# ledDisplay.net
KiCad netlist of a schematic drawn in EAGLE
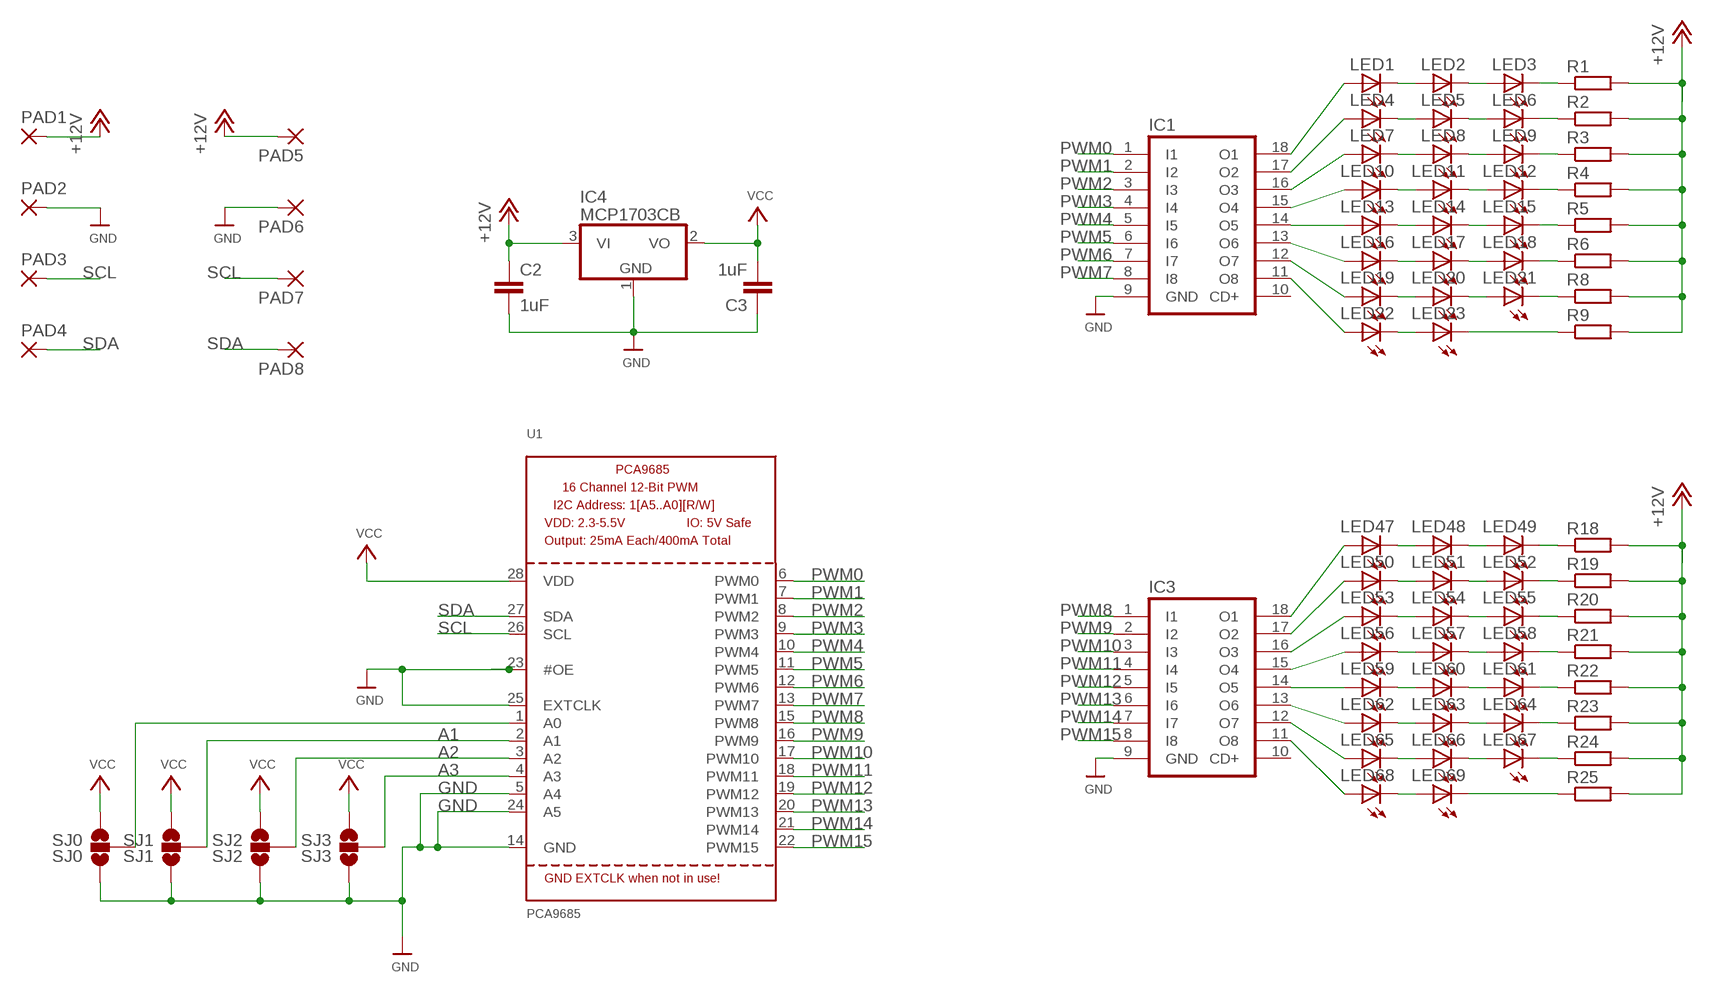
[diagram p0: schematic, sheet 1]

(export (version "E")
  (design (tool "Eeschema 10.0.6"))
  (components
    (comp (ref "C2")
      (value "1uF")
      (footprint "eagle-import:C1206")
      (libsource (lib "eagle-import") (part "C-EUC1206"))
    )
    (comp (ref "C3")
      (value "1uF")
      (footprint "eagle-import:C1206")
      (libsource (lib "eagle-import") (part "C-EUC1206"))
    )
    (comp (ref "IC1")
      (value "ULN2803A")
      (footprint "eagle-import:SO18W")
      (libsource (lib "eagle-import") (part "ULN2803A"))
    )
    (comp (ref "IC3")
      (value "ULN2803AIC")
      (footprint "eagle-import:DIL18")
      (libsource (lib "eagle-import") (part "ULN2803AIC"))
    )
    (comp (ref "IC4")
      (value "MCP1703CB")
      (footprint "eagle-import:SOT23")
      (libsource (lib "eagle-import") (part "MCP1703CB"))
    )
    (comp (ref "LED1")
      (value "LED5MM")
      (footprint "eagle-import:LED5MM")
      (libsource (lib "eagle-import") (part "LED5MM"))
    )
    (comp (ref "LED2")
      (value "LED5MM")
      (footprint "eagle-import:LED5MM")
      (libsource (lib "eagle-import") (part "LED5MM"))
    )
    (comp (ref "LED3")
      (value "LED5MM")
      (footprint "eagle-import:LED5MM")
      (libsource (lib "eagle-import") (part "LED5MM"))
    )
    (comp (ref "LED4")
      (value "LED5MM")
      (footprint "eagle-import:LED5MM")
      (libsource (lib "eagle-import") (part "LED5MM"))
    )
    (comp (ref "LED5")
      (value "LED5MM")
      (footprint "eagle-import:LED5MM")
      (libsource (lib "eagle-import") (part "LED5MM"))
    )
    (comp (ref "LED6")
      (value "LED5MM")
      (footprint "eagle-import:LED5MM")
      (libsource (lib "eagle-import") (part "LED5MM"))
    )
    (comp (ref "LED7")
      (value "LED5MM")
      (footprint "eagle-import:LED5MM")
      (libsource (lib "eagle-import") (part "LED5MM"))
    )
    (comp (ref "LED8")
      (value "LED5MM")
      (footprint "eagle-import:LED5MM")
      (libsource (lib "eagle-import") (part "LED5MM"))
    )
    (comp (ref "LED9")
      (value "LED5MM")
      (footprint "eagle-import:LED5MM")
      (libsource (lib "eagle-import") (part "LED5MM"))
    )
    (comp (ref "LED10")
      (value "LED5MM")
      (footprint "eagle-import:LED5MM")
      (libsource (lib "eagle-import") (part "LED5MM"))
    )
    (comp (ref "LED11")
      (value "LED5MM")
      (footprint "eagle-import:LED5MM")
      (libsource (lib "eagle-import") (part "LED5MM"))
    )
    (comp (ref "LED12")
      (value "LED5MM")
      (footprint "eagle-import:LED5MM")
      (libsource (lib "eagle-import") (part "LED5MM"))
    )
    (comp (ref "LED13")
      (value "LED5MM")
      (footprint "eagle-import:LED5MM")
      (libsource (lib "eagle-import") (part "LED5MM"))
    )
    (comp (ref "LED14")
      (value "LED5MM")
      (footprint "eagle-import:LED5MM")
      (libsource (lib "eagle-import") (part "LED5MM"))
    )
    (comp (ref "LED15")
      (value "LED5MM")
      (footprint "eagle-import:LED5MM")
      (libsource (lib "eagle-import") (part "LED5MM"))
    )
    (comp (ref "LED16")
      (value "LED5MM")
      (footprint "eagle-import:LED5MM")
      (libsource (lib "eagle-import") (part "LED5MM"))
    )
    (comp (ref "LED17")
      (value "LED5MM")
      (footprint "eagle-import:LED5MM")
      (libsource (lib "eagle-import") (part "LED5MM"))
    )
    (comp (ref "LED18")
      (value "LED5MM")
      (footprint "eagle-import:LED5MM")
      (libsource (lib "eagle-import") (part "LED5MM"))
    )
    (comp (ref "LED19")
      (value "LED5MM")
      (footprint "eagle-import:LED5MM")
      (libsource (lib "eagle-import") (part "LED5MM"))
    )
    (comp (ref "LED20")
      (value "LED5MM")
      (footprint "eagle-import:LED5MM")
      (libsource (lib "eagle-import") (part "LED5MM"))
    )
    (comp (ref "LED21")
      (value "LED5MM")
      (footprint "eagle-import:LED5MM")
      (libsource (lib "eagle-import") (part "LED5MM"))
    )
    (comp (ref "LED22")
      (value "LED5MM")
      (footprint "eagle-import:LED5MM")
      (libsource (lib "eagle-import") (part "LED5MM"))
    )
    (comp (ref "LED23")
      (value "LED5MM")
      (footprint "eagle-import:LED5MM")
      (libsource (lib "eagle-import") (part "LED5MM"))
    )
    (comp (ref "LED47")
      (value "LED5MM")
      (footprint "eagle-import:LED5MM")
      (libsource (lib "eagle-import") (part "LED5MM"))
    )
    (comp (ref "LED48")
      (value "LED5MM")
      (footprint "eagle-import:LED5MM")
      (libsource (lib "eagle-import") (part "LED5MM"))
    )
    (comp (ref "LED49")
      (value "LED5MM")
      (footprint "eagle-import:LED5MM")
      (libsource (lib "eagle-import") (part "LED5MM"))
    )
    (comp (ref "LED50")
      (value "LED5MM")
      (footprint "eagle-import:LED5MM")
      (libsource (lib "eagle-import") (part "LED5MM"))
    )
    (comp (ref "LED51")
      (value "LED5MM")
      (footprint "eagle-import:LED5MM")
      (libsource (lib "eagle-import") (part "LED5MM"))
    )
    (comp (ref "LED52")
      (value "LED5MM")
      (footprint "eagle-import:LED5MM")
      (libsource (lib "eagle-import") (part "LED5MM"))
    )
    (comp (ref "LED53")
      (value "LED5MM")
      (footprint "eagle-import:LED5MM")
      (libsource (lib "eagle-import") (part "LED5MM"))
    )
    (comp (ref "LED54")
      (value "LED5MM")
      (footprint "eagle-import:LED5MM")
      (libsource (lib "eagle-import") (part "LED5MM"))
    )
    (comp (ref "LED55")
      (value "LED5MM")
      (footprint "eagle-import:LED5MM")
      (libsource (lib "eagle-import") (part "LED5MM"))
    )
    (comp (ref "LED56")
      (value "LED5MM")
      (footprint "eagle-import:LED5MM")
      (libsource (lib "eagle-import") (part "LED5MM"))
    )
    (comp (ref "LED57")
      (value "LED5MM")
      (footprint "eagle-import:LED5MM")
      (libsource (lib "eagle-import") (part "LED5MM"))
    )
    (comp (ref "LED58")
      (value "LED5MM")
      (footprint "eagle-import:LED5MM")
      (libsource (lib "eagle-import") (part "LED5MM"))
    )
    (comp (ref "LED59")
      (value "LED5MM")
      (footprint "eagle-import:LED5MM")
      (libsource (lib "eagle-import") (part "LED5MM"))
    )
    (comp (ref "LED60")
      (value "LED5MM")
      (footprint "eagle-import:LED5MM")
      (libsource (lib "eagle-import") (part "LED5MM"))
    )
    (comp (ref "LED61")
      (value "LED5MM")
      (footprint "eagle-import:LED5MM")
      (libsource (lib "eagle-import") (part "LED5MM"))
    )
    (comp (ref "LED62")
      (value "LED5MM")
      (footprint "eagle-import:LED5MM")
      (libsource (lib "eagle-import") (part "LED5MM"))
    )
    (comp (ref "LED63")
      (value "LED5MM")
      (footprint "eagle-import:LED5MM")
      (libsource (lib "eagle-import") (part "LED5MM"))
    )
    (comp (ref "LED64")
      (value "LED5MM")
      (footprint "eagle-import:LED5MM")
      (libsource (lib "eagle-import") (part "LED5MM"))
    )
    (comp (ref "LED65")
      (value "LED5MM")
      (footprint "eagle-import:LED5MM")
      (libsource (lib "eagle-import") (part "LED5MM"))
    )
    (comp (ref "LED66")
      (value "LED5MM")
      (footprint "eagle-import:LED5MM")
      (libsource (lib "eagle-import") (part "LED5MM"))
    )
    (comp (ref "LED67")
      (value "LED5MM")
      (footprint "eagle-import:LED5MM")
      (libsource (lib "eagle-import") (part "LED5MM"))
    )
    (comp (ref "LED68")
      (value "LED5MM")
      (footprint "eagle-import:LED5MM")
      (libsource (lib "eagle-import") (part "LED5MM"))
    )
    (comp (ref "LED69")
      (value "LED5MM")
      (footprint "eagle-import:LED5MM")
      (libsource (lib "eagle-import") (part "LED5MM"))
    )
    (comp (ref "PAD1")
      (value "SMD5")
      (footprint "eagle-import:SMD2,54-5,08")
      (libsource (lib "eagle-import") (part "SMD5"))
    )
    (comp (ref "PAD2")
      (value "SMD5")
      (footprint "eagle-import:SMD2,54-5,08")
      (libsource (lib "eagle-import") (part "SMD5"))
    )
    (comp (ref "PAD3")
      (value "SMD5")
      (footprint "eagle-import:SMD2,54-5,08")
      (libsource (lib "eagle-import") (part "SMD5"))
    )
    (comp (ref "PAD4")
      (value "SMD5")
      (footprint "eagle-import:SMD2,54-5,08")
      (libsource (lib "eagle-import") (part "SMD5"))
    )
    (comp (ref "PAD5")
      (value "SMD5")
      (footprint "eagle-import:SMD2,54-5,08")
      (libsource (lib "eagle-import") (part "SMD5"))
    )
    (comp (ref "PAD6")
      (value "SMD5")
      (footprint "eagle-import:SMD2,54-5,08")
      (libsource (lib "eagle-import") (part "SMD5"))
    )
    (comp (ref "PAD7")
      (value "SMD5")
      (footprint "eagle-import:SMD2,54-5,08")
      (libsource (lib "eagle-import") (part "SMD5"))
    )
    (comp (ref "PAD8")
      (value "SMD5")
      (footprint "eagle-import:SMD2,54-5,08")
      (libsource (lib "eagle-import") (part "SMD5"))
    )
    (comp (ref "R1")
      (value "R-EU_0204/7")
      (footprint "eagle-import:0204_7")
      (libsource (lib "eagle-import") (part "R-EU_0204/7"))
    )
    (comp (ref "R2")
      (value "R-EU_0204/7")
      (footprint "eagle-import:0204_7")
      (libsource (lib "eagle-import") (part "R-EU_0204/7"))
    )
    (comp (ref "R3")
      (value "R-EU_0204/7")
      (footprint "eagle-import:0204_7")
      (libsource (lib "eagle-import") (part "R-EU_0204/7"))
    )
    (comp (ref "R4")
      (value "R-EU_0204/7")
      (footprint "eagle-import:0204_7")
      (libsource (lib "eagle-import") (part "R-EU_0204/7"))
    )
    (comp (ref "R5")
      (value "R-EU_0204/7")
      (footprint "eagle-import:0204_7")
      (libsource (lib "eagle-import") (part "R-EU_0204/7"))
    )
    (comp (ref "R6")
      (value "R-EU_0204/7")
      (footprint "eagle-import:0204_7")
      (libsource (lib "eagle-import") (part "R-EU_0204/7"))
    )
    (comp (ref "R8")
      (value "R-EU_0204/7")
      (footprint "eagle-import:0204_7")
      (libsource (lib "eagle-import") (part "R-EU_0204/7"))
    )
    (comp (ref "R9")
      (value "R-EU_0204/7")
      (footprint "eagle-import:0204_7")
      (libsource (lib "eagle-import") (part "R-EU_0204/7"))
    )
    (comp (ref "R18")
      (value "R-EU_0204/7")
      (footprint "eagle-import:0204_7")
      (libsource (lib "eagle-import") (part "R-EU_0204/7"))
    )
    (comp (ref "R19")
      (value "R-EU_0204/7")
      (footprint "eagle-import:0204_7")
      (libsource (lib "eagle-import") (part "R-EU_0204/7"))
    )
    (comp (ref "R20")
      (value "R-EU_0204/7")
      (footprint "eagle-import:0204_7")
      (libsource (lib "eagle-import") (part "R-EU_0204/7"))
    )
    (comp (ref "R21")
      (value "R-EU_0204/7")
      (footprint "eagle-import:0204_7")
      (libsource (lib "eagle-import") (part "R-EU_0204/7"))
    )
    (comp (ref "R22")
      (value "R-EU_0204/7")
      (footprint "eagle-import:0204_7")
      (libsource (lib "eagle-import") (part "R-EU_0204/7"))
    )
    (comp (ref "R23")
      (value "R-EU_0204/7")
      (footprint "eagle-import:0204_7")
      (libsource (lib "eagle-import") (part "R-EU_0204/7"))
    )
    (comp (ref "R24")
      (value "R-EU_0204/7")
      (footprint "eagle-import:0204_7")
      (libsource (lib "eagle-import") (part "R-EU_0204/7"))
    )
    (comp (ref "R25")
      (value "R-EU_0204/7")
      (footprint "eagle-import:0204_7")
      (libsource (lib "eagle-import") (part "R-EU_0204/7"))
    )
    (comp (ref "SJ0")
      (value "SJ0")
      (footprint "eagle-import:SJ_3")
      (libsource (lib "eagle-import") (part "SOLDERJUMPER_2WAYS"))
    )
    (comp (ref "SJ1")
      (value "SJ1")
      (footprint "eagle-import:SJ_3")
      (libsource (lib "eagle-import") (part "SOLDERJUMPER_2WAYS"))
    )
    (comp (ref "SJ2")
      (value "SJ2")
      (footprint "eagle-import:SJ_3")
      (libsource (lib "eagle-import") (part "SOLDERJUMPER_2WAYS"))
    )
    (comp (ref "SJ3")
      (value "SJ3")
      (footprint "eagle-import:SJ_3")
      (libsource (lib "eagle-import") (part "SOLDERJUMPER_2WAYS"))
    )
    (comp (ref "U1")
      (value "PCA9685")
      (footprint "eagle-import:TSSOP28")
      (libsource (lib "eagle-import") (part "PCA9685"))
    )
  )
  (nets
    (net (code "1") (name "+12V") (class "Default")
      (node (ref "C2") (pin "1") (pinfunction "1_1") (pintype "passive"))
      (node (ref "IC4") (pin "3") (pinfunction "VI_3") (pintype "input"))
      (node (ref "PAD1") (pin "1") (pinfunction "P_1") (pintype "passive"))
      (node (ref "PAD5") (pin "1") (pinfunction "P_1") (pintype "passive"))
      (node (ref "R1") (pin "2") (pinfunction "2_2") (pintype "passive"))
      (node (ref "R18") (pin "2") (pinfunction "2_2") (pintype "passive"))
      (node (ref "R19") (pin "2") (pinfunction "2_2") (pintype "passive"))
      (node (ref "R2") (pin "2") (pinfunction "2_2") (pintype "passive"))
      (node (ref "R20") (pin "2") (pinfunction "2_2") (pintype "passive"))
      (node (ref "R21") (pin "2") (pinfunction "2_2") (pintype "passive"))
      (node (ref "R22") (pin "2") (pinfunction "2_2") (pintype "passive"))
      (node (ref "R23") (pin "2") (pinfunction "2_2") (pintype "passive"))
      (node (ref "R24") (pin "2") (pinfunction "2_2") (pintype "passive"))
      (node (ref "R25") (pin "2") (pinfunction "2_2") (pintype "passive"))
      (node (ref "R3") (pin "2") (pinfunction "2_2") (pintype "passive"))
      (node (ref "R4") (pin "2") (pinfunction "2_2") (pintype "passive"))
      (node (ref "R5") (pin "2") (pinfunction "2_2") (pintype "passive"))
      (node (ref "R6") (pin "2") (pinfunction "2_2") (pintype "passive"))
      (node (ref "R8") (pin "2") (pinfunction "2_2") (pintype "passive"))
      (node (ref "R9") (pin "2") (pinfunction "2_2") (pintype "passive"))
    )
    (net (code "2") (name "A1") (class "Default")
      (node (ref "SJ1") (pin "2") (pinfunction "2_2") (pintype "passive"))
      (node (ref "U1") (pin "2") (pinfunction "A1_2") (pintype "bidirectional"))
    )
    (net (code "3") (name "A2") (class "Default")
      (node (ref "SJ2") (pin "2") (pinfunction "2_2") (pintype "passive"))
      (node (ref "U1") (pin "3") (pinfunction "A2_3") (pintype "bidirectional"))
    )
    (net (code "4") (name "A3") (class "Default")
      (node (ref "SJ3") (pin "2") (pinfunction "2_2") (pintype "passive"))
      (node (ref "U1") (pin "4") (pinfunction "A3_4") (pintype "bidirectional"))
    )
    (net (code "5") (name "GND") (class "Default")
      (node (ref "C2") (pin "2") (pinfunction "2_2") (pintype "passive"))
      (node (ref "C3") (pin "1") (pinfunction "1_1") (pintype "passive"))
      (node (ref "IC1") (pin "9") (pinfunction "GND_9") (pintype "power_in"))
      (node (ref "IC3") (pin "9") (pinfunction "GND_9") (pintype "power_in"))
      (node (ref "IC4") (pin "1") (pinfunction "GND_1") (pintype "passive"))
      (node (ref "PAD2") (pin "1") (pinfunction "P_1") (pintype "passive"))
      (node (ref "PAD6") (pin "1") (pinfunction "P_1") (pintype "passive"))
      (node (ref "SJ0") (pin "1") (pinfunction "1_1") (pintype "passive"))
      (node (ref "SJ1") (pin "1") (pinfunction "1_1") (pintype "passive"))
      (node (ref "SJ2") (pin "1") (pinfunction "1_1") (pintype "passive"))
      (node (ref "SJ3") (pin "1") (pinfunction "1_1") (pintype "passive"))
      (node (ref "U1") (pin "14") (pinfunction "GND_14") (pintype "power_in"))
      (node (ref "U1") (pin "23") (pinfunction "#OE_23") (pintype "input"))
      (node (ref "U1") (pin "24") (pinfunction "A5_24") (pintype "bidirectional"))
      (node (ref "U1") (pin "25") (pinfunction "EXTCLK_25") (pintype "input"))
      (node (ref "U1") (pin "5") (pinfunction "A4_5") (pintype "bidirectional"))
    )
    (net (code "6") (name "Net-(IC1-O1)") (class "Default")
      (node (ref "IC1") (pin "18") (pinfunction "O1_18") (pintype "open_collector"))
      (node (ref "LED1") (pin "A") (pinfunction "A_A") (pintype "passive"))
    )
    (net (code "7") (name "Net-(IC1-O2)") (class "Default")
      (node (ref "IC1") (pin "17") (pinfunction "O2_17") (pintype "open_collector"))
      (node (ref "LED4") (pin "A") (pinfunction "A_A") (pintype "passive"))
    )
    (net (code "8") (name "Net-(IC1-O3)") (class "Default")
      (node (ref "IC1") (pin "16") (pinfunction "O3_16") (pintype "open_collector"))
      (node (ref "LED7") (pin "A") (pinfunction "A_A") (pintype "passive"))
    )
    (net (code "9") (name "Net-(IC1-O4)") (class "Default")
      (node (ref "IC1") (pin "15") (pinfunction "O4_15") (pintype "open_collector"))
      (node (ref "LED10") (pin "A") (pinfunction "A_A") (pintype "passive"))
    )
    (net (code "10") (name "Net-(IC1-O5)") (class "Default")
      (node (ref "IC1") (pin "14") (pinfunction "O5_14") (pintype "open_collector"))
      (node (ref "LED13") (pin "A") (pinfunction "A_A") (pintype "passive"))
    )
    (net (code "11") (name "Net-(IC1-O6)") (class "Default")
      (node (ref "IC1") (pin "13") (pinfunction "O6_13") (pintype "open_collector"))
      (node (ref "LED16") (pin "A") (pinfunction "A_A") (pintype "passive"))
    )
    (net (code "12") (name "Net-(IC1-O7)") (class "Default")
      (node (ref "IC1") (pin "12") (pinfunction "O7_12") (pintype "open_collector"))
      (node (ref "LED19") (pin "A") (pinfunction "A_A") (pintype "passive"))
    )
    (net (code "13") (name "Net-(IC1-O8)") (class "Default")
      (node (ref "IC1") (pin "11") (pinfunction "O8_11") (pintype "open_collector"))
      (node (ref "LED22") (pin "A") (pinfunction "A_A") (pintype "passive"))
    )
    (net (code "14") (name "Net-(IC3-O1)") (class "Default")
      (node (ref "IC3") (pin "18") (pinfunction "O1_18") (pintype "open_collector"))
      (node (ref "LED47") (pin "A") (pinfunction "A_A") (pintype "passive"))
    )
    (net (code "15") (name "Net-(IC3-O2)") (class "Default")
      (node (ref "IC3") (pin "17") (pinfunction "O2_17") (pintype "open_collector"))
      (node (ref "LED50") (pin "A") (pinfunction "A_A") (pintype "passive"))
    )
    (net (code "16") (name "Net-(IC3-O3)") (class "Default")
      (node (ref "IC3") (pin "16") (pinfunction "O3_16") (pintype "open_collector"))
      (node (ref "LED53") (pin "A") (pinfunction "A_A") (pintype "passive"))
    )
    (net (code "17") (name "Net-(IC3-O4)") (class "Default")
      (node (ref "IC3") (pin "15") (pinfunction "O4_15") (pintype "open_collector"))
      (node (ref "LED56") (pin "A") (pinfunction "A_A") (pintype "passive"))
    )
    (net (code "18") (name "Net-(IC3-O5)") (class "Default")
      (node (ref "IC3") (pin "14") (pinfunction "O5_14") (pintype "open_collector"))
      (node (ref "LED59") (pin "A") (pinfunction "A_A") (pintype "passive"))
    )
    (net (code "19") (name "Net-(IC3-O6)") (class "Default")
      (node (ref "IC3") (pin "13") (pinfunction "O6_13") (pintype "open_collector"))
      (node (ref "LED62") (pin "A") (pinfunction "A_A") (pintype "passive"))
    )
    (net (code "20") (name "Net-(IC3-O7)") (class "Default")
      (node (ref "IC3") (pin "12") (pinfunction "O7_12") (pintype "open_collector"))
      (node (ref "LED65") (pin "A") (pinfunction "A_A") (pintype "passive"))
    )
    (net (code "21") (name "Net-(IC3-O8)") (class "Default")
      (node (ref "IC3") (pin "11") (pinfunction "O8_11") (pintype "open_collector"))
      (node (ref "LED68") (pin "A") (pinfunction "A_A") (pintype "passive"))
    )
    (net (code "22") (name "Net-(LED1-C)") (class "Default")
      (node (ref "LED1") (pin "K") (pinfunction "C_K") (pintype "passive"))
      (node (ref "LED2") (pin "A") (pinfunction "A_A") (pintype "passive"))
    )
    (net (code "23") (name "Net-(LED2-C)") (class "Default")
      (node (ref "LED2") (pin "K") (pinfunction "C_K") (pintype "passive"))
      (node (ref "LED3") (pin "A") (pinfunction "A_A") (pintype "passive"))
    )
    (net (code "24") (name "Net-(LED3-C)") (class "Default")
      (node (ref "LED3") (pin "K") (pinfunction "C_K") (pintype "passive"))
      (node (ref "R1") (pin "1") (pinfunction "1_1") (pintype "passive"))
    )
    (net (code "25") (name "Net-(LED4-C)") (class "Default")
      (node (ref "LED4") (pin "K") (pinfunction "C_K") (pintype "passive"))
      (node (ref "LED5") (pin "A") (pinfunction "A_A") (pintype "passive"))
    )
    (net (code "26") (name "Net-(LED5-C)") (class "Default")
      (node (ref "LED5") (pin "K") (pinfunction "C_K") (pintype "passive"))
      (node (ref "LED6") (pin "A") (pinfunction "A_A") (pintype "passive"))
    )
    (net (code "27") (name "Net-(LED6-C)") (class "Default")
      (node (ref "LED6") (pin "K") (pinfunction "C_K") (pintype "passive"))
      (node (ref "R2") (pin "1") (pinfunction "1_1") (pintype "passive"))
    )
    (net (code "28") (name "Net-(LED7-C)") (class "Default")
      (node (ref "LED7") (pin "K") (pinfunction "C_K") (pintype "passive"))
      (node (ref "LED8") (pin "A") (pinfunction "A_A") (pintype "passive"))
    )
    (net (code "29") (name "Net-(LED8-C)") (class "Default")
      (node (ref "LED8") (pin "K") (pinfunction "C_K") (pintype "passive"))
      (node (ref "LED9") (pin "A") (pinfunction "A_A") (pintype "passive"))
    )
    (net (code "30") (name "Net-(LED9-C)") (class "Default")
      (node (ref "LED9") (pin "K") (pinfunction "C_K") (pintype "passive"))
      (node (ref "R3") (pin "1") (pinfunction "1_1") (pintype "passive"))
    )
    (net (code "31") (name "Net-(LED10-C)") (class "Default")
      (node (ref "LED10") (pin "K") (pinfunction "C_K") (pintype "passive"))
      (node (ref "LED11") (pin "A") (pinfunction "A_A") (pintype "passive"))
    )
    (net (code "32") (name "Net-(LED11-C)") (class "Default")
      (node (ref "LED11") (pin "K") (pinfunction "C_K") (pintype "passive"))
      (node (ref "LED12") (pin "A") (pinfunction "A_A") (pintype "passive"))
    )
    (net (code "33") (name "Net-(LED12-C)") (class "Default")
      (node (ref "LED12") (pin "K") (pinfunction "C_K") (pintype "passive"))
      (node (ref "R4") (pin "1") (pinfunction "1_1") (pintype "passive"))
    )
    (net (code "34") (name "Net-(LED13-C)") (class "Default")
      (node (ref "LED13") (pin "K") (pinfunction "C_K") (pintype "passive"))
      (node (ref "LED14") (pin "A") (pinfunction "A_A") (pintype "passive"))
    )
    (net (code "35") (name "Net-(LED14-C)") (class "Default")
      (node (ref "LED14") (pin "K") (pinfunction "C_K") (pintype "passive"))
      (node (ref "LED15") (pin "A") (pinfunction "A_A") (pintype "passive"))
    )
    (net (code "36") (name "Net-(LED15-C)") (class "Default")
      (node (ref "LED15") (pin "K") (pinfunction "C_K") (pintype "passive"))
      (node (ref "R5") (pin "1") (pinfunction "1_1") (pintype "passive"))
    )
    (net (code "37") (name "Net-(LED16-C)") (class "Default")
      (node (ref "LED16") (pin "K") (pinfunction "C_K") (pintype "passive"))
      (node (ref "LED17") (pin "A") (pinfunction "A_A") (pintype "passive"))
    )
    (net (code "38") (name "Net-(LED17-C)") (class "Default")
      (node (ref "LED17") (pin "K") (pinfunction "C_K") (pintype "passive"))
      (node (ref "LED18") (pin "A") (pinfunction "A_A") (pintype "passive"))
    )
    (net (code "39") (name "Net-(LED18-C)") (class "Default")
      (node (ref "LED18") (pin "K") (pinfunction "C_K") (pintype "passive"))
      (node (ref "R6") (pin "1") (pinfunction "1_1") (pintype "passive"))
    )
    (net (code "40") (name "Net-(LED19-C)") (class "Default")
      (node (ref "LED19") (pin "K") (pinfunction "C_K") (pintype "passive"))
      (node (ref "LED20") (pin "A") (pinfunction "A_A") (pintype "passive"))
    )
    (net (code "41") (name "Net-(LED20-C)") (class "Default")
      (node (ref "LED20") (pin "K") (pinfunction "C_K") (pintype "passive"))
      (node (ref "LED21") (pin "A") (pinfunction "A_A") (pintype "passive"))
    )
    (net (code "42") (name "Net-(LED21-C)") (class "Default")
      (node (ref "LED21") (pin "K") (pinfunction "C_K") (pintype "passive"))
      (node (ref "R8") (pin "1") (pinfunction "1_1") (pintype "passive"))
    )
    (net (code "43") (name "Net-(LED22-C)") (class "Default")
      (node (ref "LED22") (pin "K") (pinfunction "C_K") (pintype "passive"))
      (node (ref "LED23") (pin "A") (pinfunction "A_A") (pintype "passive"))
    )
    (net (code "44") (name "Net-(LED23-C)") (class "Default")
      (node (ref "LED23") (pin "K") (pinfunction "C_K") (pintype "passive"))
      (node (ref "R9") (pin "1") (pinfunction "1_1") (pintype "passive"))
    )
    (net (code "45") (name "Net-(LED47-C)") (class "Default")
      (node (ref "LED47") (pin "K") (pinfunction "C_K") (pintype "passive"))
      (node (ref "LED48") (pin "A") (pinfunction "A_A") (pintype "passive"))
    )
    (net (code "46") (name "Net-(LED48-C)") (class "Default")
      (node (ref "LED48") (pin "K") (pinfunction "C_K") (pintype "passive"))
      (node (ref "LED49") (pin "A") (pinfunction "A_A") (pintype "passive"))
    )
    (net (code "47") (name "Net-(LED49-C)") (class "Default")
      (node (ref "LED49") (pin "K") (pinfunction "C_K") (pintype "passive"))
      (node (ref "R18") (pin "1") (pinfunction "1_1") (pintype "passive"))
    )
    (net (code "48") (name "Net-(LED50-C)") (class "Default")
      (node (ref "LED50") (pin "K") (pinfunction "C_K") (pintype "passive"))
      (node (ref "LED51") (pin "A") (pinfunction "A_A") (pintype "passive"))
    )
    (net (code "49") (name "Net-(LED51-C)") (class "Default")
      (node (ref "LED51") (pin "K") (pinfunction "C_K") (pintype "passive"))
      (node (ref "LED52") (pin "A") (pinfunction "A_A") (pintype "passive"))
    )
    (net (code "50") (name "Net-(LED52-C)") (class "Default")
      (node (ref "LED52") (pin "K") (pinfunction "C_K") (pintype "passive"))
      (node (ref "R19") (pin "1") (pinfunction "1_1") (pintype "passive"))
    )
    (net (code "51") (name "Net-(LED53-C)") (class "Default")
      (node (ref "LED53") (pin "K") (pinfunction "C_K") (pintype "passive"))
      (node (ref "LED54") (pin "A") (pinfunction "A_A") (pintype "passive"))
    )
    (net (code "52") (name "Net-(LED54-C)") (class "Default")
      (node (ref "LED54") (pin "K") (pinfunction "C_K") (pintype "passive"))
      (node (ref "LED55") (pin "A") (pinfunction "A_A") (pintype "passive"))
    )
    (net (code "53") (name "Net-(LED55-C)") (class "Default")
      (node (ref "LED55") (pin "K") (pinfunction "C_K") (pintype "passive"))
      (node (ref "R20") (pin "1") (pinfunction "1_1") (pintype "passive"))
    )
    (net (code "54") (name "Net-(LED56-C)") (class "Default")
      (node (ref "LED56") (pin "K") (pinfunction "C_K") (pintype "passive"))
      (node (ref "LED57") (pin "A") (pinfunction "A_A") (pintype "passive"))
    )
    (net (code "55") (name "Net-(LED57-C)") (class "Default")
      (node (ref "LED57") (pin "K") (pinfunction "C_K") (pintype "passive"))
      (node (ref "LED58") (pin "A") (pinfunction "A_A") (pintype "passive"))
    )
    (net (code "56") (name "Net-(LED58-C)") (class "Default")
      (node (ref "LED58") (pin "K") (pinfunction "C_K") (pintype "passive"))
      (node (ref "R21") (pin "1") (pinfunction "1_1") (pintype "passive"))
    )
    (net (code "57") (name "Net-(LED59-C)") (class "Default")
      (node (ref "LED59") (pin "K") (pinfunction "C_K") (pintype "passive"))
      (node (ref "LED60") (pin "A") (pinfunction "A_A") (pintype "passive"))
    )
    (net (code "58") (name "Net-(LED60-C)") (class "Default")
      (node (ref "LED60") (pin "K") (pinfunction "C_K") (pintype "passive"))
      (node (ref "LED61") (pin "A") (pinfunction "A_A") (pintype "passive"))
    )
    (net (code "59") (name "Net-(LED61-C)") (class "Default")
      (node (ref "LED61") (pin "K") (pinfunction "C_K") (pintype "passive"))
      (node (ref "R22") (pin "1") (pinfunction "1_1") (pintype "passive"))
    )
    (net (code "60") (name "Net-(LED62-C)") (class "Default")
      (node (ref "LED62") (pin "K") (pinfunction "C_K") (pintype "passive"))
      (node (ref "LED63") (pin "A") (pinfunction "A_A") (pintype "passive"))
    )
    (net (code "61") (name "Net-(LED63-C)") (class "Default")
      (node (ref "LED63") (pin "K") (pinfunction "C_K") (pintype "passive"))
      (node (ref "LED64") (pin "A") (pinfunction "A_A") (pintype "passive"))
    )
    (net (code "62") (name "Net-(LED64-C)") (class "Default")
      (node (ref "LED64") (pin "K") (pinfunction "C_K") (pintype "passive"))
      (node (ref "R23") (pin "1") (pinfunction "1_1") (pintype "passive"))
    )
    (net (code "63") (name "Net-(LED65-C)") (class "Default")
      (node (ref "LED65") (pin "K") (pinfunction "C_K") (pintype "passive"))
      (node (ref "LED66") (pin "A") (pinfunction "A_A") (pintype "passive"))
    )
    (net (code "64") (name "Net-(LED66-C)") (class "Default")
      (node (ref "LED66") (pin "K") (pinfunction "C_K") (pintype "passive"))
      (node (ref "LED67") (pin "A") (pinfunction "A_A") (pintype "passive"))
    )
    (net (code "65") (name "Net-(LED67-C)") (class "Default")
      (node (ref "LED67") (pin "K") (pinfunction "C_K") (pintype "passive"))
      (node (ref "R24") (pin "1") (pinfunction "1_1") (pintype "passive"))
    )
    (net (code "66") (name "Net-(LED68-C)") (class "Default")
      (node (ref "LED68") (pin "K") (pinfunction "C_K") (pintype "passive"))
      (node (ref "LED69") (pin "A") (pinfunction "A_A") (pintype "passive"))
    )
    (net (code "67") (name "Net-(LED69-C)") (class "Default")
      (node (ref "LED69") (pin "K") (pinfunction "C_K") (pintype "passive"))
      (node (ref "R25") (pin "1") (pinfunction "1_1") (pintype "passive"))
    )
    (net (code "68") (name "Net-(U1-A0)") (class "Default")
      (node (ref "SJ0") (pin "2") (pinfunction "2_2") (pintype "passive"))
      (node (ref "U1") (pin "1") (pinfunction "A0_1") (pintype "bidirectional"))
    )
    (net (code "69") (name "PWM0") (class "Default")
      (node (ref "IC1") (pin "1") (pinfunction "I1_1") (pintype "input"))
      (node (ref "U1") (pin "6") (pinfunction "PWM0_6") (pintype "output"))
    )
    (net (code "70") (name "PWM1") (class "Default")
      (node (ref "IC1") (pin "2") (pinfunction "I2_2") (pintype "input"))
      (node (ref "U1") (pin "7") (pinfunction "PWM1_7") (pintype "output"))
    )
    (net (code "71") (name "PWM2") (class "Default")
      (node (ref "IC1") (pin "3") (pinfunction "I3_3") (pintype "input"))
      (node (ref "U1") (pin "8") (pinfunction "PWM2_8") (pintype "output"))
    )
    (net (code "72") (name "PWM3") (class "Default")
      (node (ref "IC1") (pin "4") (pinfunction "I4_4") (pintype "input"))
      (node (ref "U1") (pin "9") (pinfunction "PWM3_9") (pintype "output"))
    )
    (net (code "73") (name "PWM4") (class "Default")
      (node (ref "IC1") (pin "5") (pinfunction "I5_5") (pintype "input"))
      (node (ref "U1") (pin "10") (pinfunction "PWM4_10") (pintype "output"))
    )
    (net (code "74") (name "PWM5") (class "Default")
      (node (ref "IC1") (pin "6") (pinfunction "I6_6") (pintype "input"))
      (node (ref "U1") (pin "11") (pinfunction "PWM5_11") (pintype "output"))
    )
    (net (code "75") (name "PWM6") (class "Default")
      (node (ref "IC1") (pin "7") (pinfunction "I7_7") (pintype "input"))
      (node (ref "U1") (pin "12") (pinfunction "PWM6_12") (pintype "output"))
    )
    (net (code "76") (name "PWM7") (class "Default")
      (node (ref "IC1") (pin "8") (pinfunction "I8_8") (pintype "input"))
      (node (ref "U1") (pin "13") (pinfunction "PWM7_13") (pintype "output"))
    )
    (net (code "77") (name "PWM8") (class "Default")
      (node (ref "IC3") (pin "1") (pinfunction "I1_1") (pintype "input"))
      (node (ref "U1") (pin "15") (pinfunction "PWM8_15") (pintype "output"))
    )
    (net (code "78") (name "PWM9") (class "Default")
      (node (ref "IC3") (pin "2") (pinfunction "I2_2") (pintype "input"))
      (node (ref "U1") (pin "16") (pinfunction "PWM9_16") (pintype "output"))
    )
    (net (code "79") (name "PWM10") (class "Default")
      (node (ref "IC3") (pin "3") (pinfunction "I3_3") (pintype "input"))
      (node (ref "U1") (pin "17") (pinfunction "PWM10_17") (pintype "output"))
    )
    (net (code "80") (name "PWM11") (class "Default")
      (node (ref "IC3") (pin "4") (pinfunction "I4_4") (pintype "input"))
      (node (ref "U1") (pin "18") (pinfunction "PWM11_18") (pintype "output"))
    )
    (net (code "81") (name "PWM12") (class "Default")
      (node (ref "IC3") (pin "5") (pinfunction "I5_5") (pintype "input"))
      (node (ref "U1") (pin "19") (pinfunction "PWM12_19") (pintype "output"))
    )
    (net (code "82") (name "PWM13") (class "Default")
      (node (ref "IC3") (pin "6") (pinfunction "I6_6") (pintype "input"))
      (node (ref "U1") (pin "20") (pinfunction "PWM13_20") (pintype "output"))
    )
    (net (code "83") (name "PWM14") (class "Default")
      (node (ref "IC3") (pin "7") (pinfunction "I7_7") (pintype "input"))
      (node (ref "U1") (pin "21") (pinfunction "PWM14_21") (pintype "output"))
    )
    (net (code "84") (name "PWM15") (class "Default")
      (node (ref "IC3") (pin "8") (pinfunction "I8_8") (pintype "input"))
      (node (ref "U1") (pin "22") (pinfunction "PWM15_22") (pintype "output"))
    )
    (net (code "85") (name "SCL") (class "Default")
      (node (ref "PAD3") (pin "1") (pinfunction "P_1") (pintype "passive"))
      (node (ref "PAD7") (pin "1") (pinfunction "P_1") (pintype "passive"))
      (node (ref "U1") (pin "26") (pinfunction "SCL_26") (pintype "bidirectional"))
    )
    (net (code "86") (name "SDA") (class "Default")
      (node (ref "PAD4") (pin "1") (pinfunction "P_1") (pintype "passive"))
      (node (ref "PAD8") (pin "1") (pinfunction "P_1") (pintype "passive"))
      (node (ref "U1") (pin "27") (pinfunction "SDA_27") (pintype "bidirectional"))
    )
    (net (code "87") (name "VCC") (class "Default")
      (node (ref "C3") (pin "2") (pinfunction "2_2") (pintype "passive"))
      (node (ref "IC4") (pin "2") (pinfunction "VO_2") (pintype "passive"))
      (node (ref "SJ0") (pin "3") (pinfunction "3_3") (pintype "passive"))
      (node (ref "SJ1") (pin "3") (pinfunction "3_3") (pintype "passive"))
      (node (ref "SJ2") (pin "3") (pinfunction "3_3") (pintype "passive"))
      (node (ref "SJ3") (pin "3") (pinfunction "3_3") (pintype "passive"))
      (node (ref "U1") (pin "28") (pinfunction "VDD_28") (pintype "power_in"))
    )
    (net (code "88") (name "unconnected-(IC1-CD+-Pad10)") (class "Default")
      (node (ref "IC1") (pin "10") (pinfunction "CD+_10") (pintype "passive"))
    )
    (net (code "89") (name "unconnected-(IC3-CD+-Pad10)") (class "Default")
      (node (ref "IC3") (pin "10") (pinfunction "CD+_10") (pintype "passive"))
    )
  )
)
